# shield.net
KiCad netlist of a schematic drawn in EAGLE
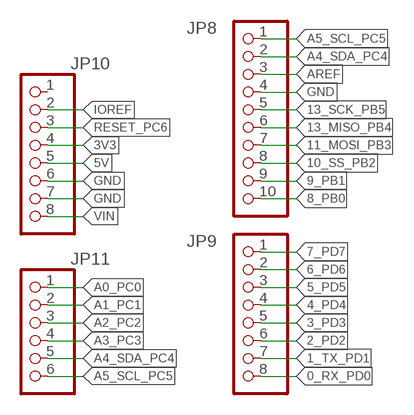
[diagram p0: schematic, sheet 1]

(export (version "E")
  (design (tool "Eeschema 10.0.6"))
  (components
    (comp (ref "JP8")
      (value "PINHD-1X10")
      (footprint "eagle-import:1X10")
      (libsource (lib "eagle-import") (part "PINHD-1X10"))
    )
    (comp (ref "JP9")
      (value "PINHD-1X8")
      (footprint "eagle-import:1X08")
      (libsource (lib "eagle-import") (part "PINHD-1X8"))
    )
    (comp (ref "JP10")
      (value "PINHD-1X8")
      (footprint "eagle-import:1X08")
      (libsource (lib "eagle-import") (part "PINHD-1X8"))
    )
    (comp (ref "JP11")
      (value "PINHD-1X6")
      (footprint "eagle-import:1X06")
      (libsource (lib "eagle-import") (part "PINHD-1X6"))
    )
  )
  (nets
    (net (code "1") (name "0_RX_PD0") (class "Default")
      (node (ref "JP9") (pin "8") (pinfunction "8_8") (pintype "passive"))
    )
    (net (code "2") (name "1_TX_PD1") (class "Default")
      (node (ref "JP9") (pin "7") (pinfunction "7_7") (pintype "passive"))
    )
    (net (code "3") (name "2_PD2") (class "Default")
      (node (ref "JP9") (pin "6") (pinfunction "6_6") (pintype "passive"))
    )
    (net (code "4") (name "3V3") (class "Default")
      (node (ref "JP10") (pin "4") (pinfunction "4_4") (pintype "passive"))
    )
    (net (code "5") (name "3_PD3") (class "Default")
      (node (ref "JP9") (pin "5") (pinfunction "5_5") (pintype "passive"))
    )
    (net (code "6") (name "4_PD4") (class "Default")
      (node (ref "JP9") (pin "4") (pinfunction "4_4") (pintype "passive"))
    )
    (net (code "7") (name "5V") (class "Default")
      (node (ref "JP10") (pin "5") (pinfunction "5_5") (pintype "passive"))
    )
    (net (code "8") (name "5_PD5") (class "Default")
      (node (ref "JP9") (pin "3") (pinfunction "3_3") (pintype "passive"))
    )
    (net (code "9") (name "6_PD6") (class "Default")
      (node (ref "JP9") (pin "2") (pinfunction "2_2") (pintype "passive"))
    )
    (net (code "10") (name "7_PD7") (class "Default")
      (node (ref "JP9") (pin "1") (pinfunction "1_1") (pintype "passive"))
    )
    (net (code "11") (name "8_PB0") (class "Default")
      (node (ref "JP8") (pin "10") (pinfunction "10_10") (pintype "passive"))
    )
    (net (code "12") (name "9_PB1") (class "Default")
      (node (ref "JP8") (pin "9") (pinfunction "9_9") (pintype "passive"))
    )
    (net (code "13") (name "10_SS_PB2") (class "Default")
      (node (ref "JP8") (pin "8") (pinfunction "8_8") (pintype "passive"))
    )
    (net (code "14") (name "11_MOSI_PB3") (class "Default")
      (node (ref "JP8") (pin "7") (pinfunction "7_7") (pintype "passive"))
    )
    (net (code "15") (name "13_MISO_PB4") (class "Default")
      (node (ref "JP8") (pin "6") (pinfunction "6_6") (pintype "passive"))
    )
    (net (code "16") (name "13_SCK_PB5") (class "Default")
      (node (ref "JP8") (pin "5") (pinfunction "5_5") (pintype "passive"))
    )
    (net (code "17") (name "A0_PC0") (class "Default")
      (node (ref "JP11") (pin "1") (pinfunction "1_1") (pintype "passive"))
    )
    (net (code "18") (name "A1_PC1") (class "Default")
      (node (ref "JP11") (pin "2") (pinfunction "2_2") (pintype "passive"))
    )
    (net (code "19") (name "A2_PC2") (class "Default")
      (node (ref "JP11") (pin "3") (pinfunction "3_3") (pintype "passive"))
    )
    (net (code "20") (name "A3_PC3") (class "Default")
      (node (ref "JP11") (pin "4") (pinfunction "4_4") (pintype "passive"))
    )
    (net (code "21") (name "A4_SDA_PC4") (class "Default")
      (node (ref "JP11") (pin "5") (pinfunction "5_5") (pintype "passive"))
      (node (ref "JP8") (pin "2") (pinfunction "2_2") (pintype "passive"))
    )
    (net (code "22") (name "A5_SCL_PC5") (class "Default")
      (node (ref "JP11") (pin "6") (pinfunction "6_6") (pintype "passive"))
      (node (ref "JP8") (pin "1") (pinfunction "1_1") (pintype "passive"))
    )
    (net (code "23") (name "AREF") (class "Default")
      (node (ref "JP8") (pin "3") (pinfunction "3_3") (pintype "passive"))
    )
    (net (code "24") (name "GND") (class "Default")
      (node (ref "JP10") (pin "6") (pinfunction "6_6") (pintype "passive"))
      (node (ref "JP10") (pin "7") (pinfunction "7_7") (pintype "passive"))
      (node (ref "JP8") (pin "4") (pinfunction "4_4") (pintype "passive"))
    )
    (net (code "25") (name "IOREF") (class "Default")
      (node (ref "JP10") (pin "2") (pinfunction "2_2") (pintype "passive"))
    )
    (net (code "26") (name "RESET_PC6") (class "Default")
      (node (ref "JP10") (pin "3") (pinfunction "3_3") (pintype "passive"))
    )
    (net (code "27") (name "VIN") (class "Default")
      (node (ref "JP10") (pin "8") (pinfunction "8_8") (pintype "passive"))
    )
    (net (code "28") (name "unconnected-(JP10-Pad1)") (class "Default")
      (node (ref "JP10") (pin "1") (pinfunction "1_1") (pintype "passive"))
    )
  )
)
